# Mosfet_Driver.net
KiCad netlist of a schematic drawn in Altium Designer
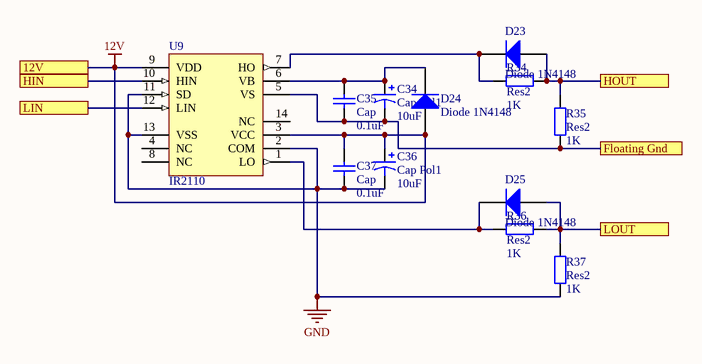
[diagram p0: Mosfet Driver.SchDoc]

(export (version "E")
  (design (tool "Eeschema 10.0.6"))
  (components
    (comp (ref "C34")
      (value "Cap Pol1")
      (footprint "RB7.6-15")
      (description "Polarized Capacitor (Radial)")
      (fields (field (name "ALTIUM_VALUE") "10uF") (field (name "PUBLISHER") "Altium Limited"))
      (libsource (lib "Miscellaneous Devices") (part "Cap Pol1"))
    )
    (comp (ref "C35")
      (value "Cap")
      (footprint "RAD-0.3")
      (description "Capacitor")
      (fields (field (name "ALTIUM_VALUE") "0.1uF") (field (name "PUBLISHER") "Altium Limited"))
      (libsource (lib "Miscellaneous Devices") (part "Cap"))
    )
    (comp (ref "C36")
      (value "Cap Pol1")
      (footprint "RB7.6-15")
      (description "Polarized Capacitor (Radial)")
      (fields (field (name "ALTIUM_VALUE") "10uF") (field (name "PUBLISHER") "Altium Limited"))
      (libsource (lib "Miscellaneous Devices") (part "Cap Pol1"))
    )
    (comp (ref "C37")
      (value "Cap")
      (footprint "RAD-0.3")
      (description "Capacitor")
      (fields (field (name "ALTIUM_VALUE") "0.1uF") (field (name "PUBLISHER") "Altium Limited"))
      (libsource (lib "Miscellaneous Devices") (part "Cap"))
    )
    (comp (ref "D23")
      (value "Diode 1N4148")
      (footprint "DO-35")
      (description "High Conductance Fast Diode")
      (fields (field (name "PUBLISHER") "Altium Limited"))
      (libsource (lib "Miscellaneous Devices") (part "Diode 1N4148"))
    )
    (comp (ref "D24")
      (value "Diode 1N4148")
      (footprint "DO-35")
      (description "High Conductance Fast Diode")
      (fields (field (name "PUBLISHER") "Altium Limited"))
      (libsource (lib "Miscellaneous Devices") (part "Diode 1N4148"))
    )
    (comp (ref "D25")
      (value "Diode 1N4148")
      (footprint "DO-35")
      (description "High Conductance Fast Diode")
      (fields (field (name "PUBLISHER") "Altium Limited"))
      (libsource (lib "Miscellaneous Devices") (part "Diode 1N4148"))
    )
    (comp (ref "R34")
      (value "Res2")
      (footprint "AXIAL-0.4")
      (description "Resistor")
      (fields (field (name "ALTIUM_VALUE") "1K") (field (name "PUBLISHER") "Altium Limited"))
      (libsource (lib "") (part "Res2_2"))
    )
    (comp (ref "R35")
      (value "Res2")
      (footprint "AXIAL-0.4")
      (description "Resistor")
      (fields (field (name "ALTIUM_VALUE") "1K") (field (name "PUBLISHER") "Altium Limited"))
      (libsource (lib "") (part "Res2_1"))
    )
    (comp (ref "R36")
      (value "Res2")
      (footprint "AXIAL-0.4")
      (description "Resistor")
      (fields (field (name "ALTIUM_VALUE") "1K") (field (name "PUBLISHER") "Altium Limited"))
      (libsource (lib "") (part "Res2_3"))
    )
    (comp (ref "R37")
      (value "Res2")
      (footprint "AXIAL-0.4")
      (description "Resistor")
      (fields (field (name "ALTIUM_VALUE") "1K") (field (name "PUBLISHER") "Altium Limited"))
      (libsource (lib "Miscellaneous Devices") (part "Res2"))
    )
    (comp (ref "U9")
      (value "IR2110")
      (footprint "PDIP14")
      (description "High and Low Side Driver")
      (fields (field (name "PUBLISHER") "Altium Limited"))
      (libsource (lib "IR Interface Bridge Driver") (part "IR2110"))
    )
  )
  (nets
    (net (code "1") (name "/Floating Gnd") (class "Default")
      (node (ref "C34") (pin "2") (pinfunction "2_2") (pintype "passive"))
      (node (ref "C35") (pin "1") (pinfunction "1_1") (pintype "passive"))
      (node (ref "R35") (pin "1") (pinfunction "1_1") (pintype "passive"))
      (node (ref "U9") (pin "5") (pinfunction "VS_5") (pintype "power_in"))
    )
    (net (code "2") (name "/HIN") (class "Default")
      (node (ref "U9") (pin "10") (pinfunction "HIN_10") (pintype "input"))
    )
    (net (code "3") (name "/HOUT") (class "Default")
      (node (ref "D23") (pin "1") (pinfunction "A_1") (pintype "passive"))
      (node (ref "R34") (pin "2") (pinfunction "2_2") (pintype "passive"))
      (node (ref "R35") (pin "2") (pinfunction "2_2") (pintype "passive"))
    )
    (net (code "4") (name "/LIN") (class "Default")
      (node (ref "U9") (pin "12") (pinfunction "LIN_12") (pintype "input"))
    )
    (net (code "5") (name "/LOUT") (class "Default")
      (node (ref "D25") (pin "1") (pinfunction "A_1") (pintype "passive"))
      (node (ref "R36") (pin "1") (pinfunction "1_1") (pintype "passive"))
      (node (ref "R37") (pin "1") (pinfunction "1_1") (pintype "passive"))
    )
    (net (code "6") (name "12V") (class "Default")
      (node (ref "C36") (pin "1") (pinfunction "1_1") (pintype "passive"))
      (node (ref "C37") (pin "2") (pinfunction "2_2") (pintype "passive"))
      (node (ref "D24") (pin "1") (pinfunction "A_1") (pintype "passive"))
      (node (ref "U9") (pin "3") (pinfunction "VCC_3") (pintype "power_in"))
      (node (ref "U9") (pin "9") (pinfunction "VDD_9") (pintype "power_in"))
    )
    (net (code "7") (name "GND") (class "Default")
      (node (ref "C36") (pin "2") (pinfunction "2_2") (pintype "passive"))
      (node (ref "C37") (pin "1") (pinfunction "1_1") (pintype "passive"))
      (node (ref "R37") (pin "2") (pinfunction "2_2") (pintype "passive"))
      (node (ref "U9") (pin "11") (pinfunction "SD_11") (pintype "input"))
      (node (ref "U9") (pin "13") (pinfunction "VSS_13") (pintype "power_in"))
      (node (ref "U9") (pin "2") (pinfunction "COM_2") (pintype "power_in"))
    )
    (net (code "8") (name "Net-(D23-K)") (class "Default")
      (node (ref "D23") (pin "2") (pinfunction "K_2") (pintype "passive"))
      (node (ref "R34") (pin "1") (pinfunction "1_1") (pintype "passive"))
      (node (ref "U9") (pin "7") (pinfunction "HO_7") (pintype "output"))
    )
    (net (code "9") (name "Net-(D24-K)") (class "Default")
      (node (ref "C34") (pin "1") (pinfunction "1_1") (pintype "passive"))
      (node (ref "C35") (pin "2") (pinfunction "2_2") (pintype "passive"))
      (node (ref "D24") (pin "2") (pinfunction "K_2") (pintype "passive"))
      (node (ref "U9") (pin "6") (pinfunction "VB_6") (pintype "power_in"))
    )
    (net (code "10") (name "Net-(D25-K)") (class "Default")
      (node (ref "D25") (pin "2") (pinfunction "K_2") (pintype "passive"))
      (node (ref "R36") (pin "2") (pinfunction "2_2") (pintype "passive"))
      (node (ref "U9") (pin "1") (pinfunction "LO_1") (pintype "output"))
    )
    (net (code "11") (name "unconnected-(U9-NC-Pad4)") (class "Default")
      (node (ref "U9") (pin "4") (pinfunction "NC_4") (pintype "passive"))
    )
    (net (code "12") (name "unconnected-(U9-NC-Pad8)") (class "Default")
      (node (ref "U9") (pin "8") (pinfunction "NC_8") (pintype "passive"))
    )
    (net (code "13") (name "unconnected-(U9-NC-Pad14)") (class "Default")
      (node (ref "U9") (pin "14") (pinfunction "NC_14") (pintype "passive"))
    )
  )
)
